# tinyape.net
KiCad netlist of a schematic drawn in EAGLE
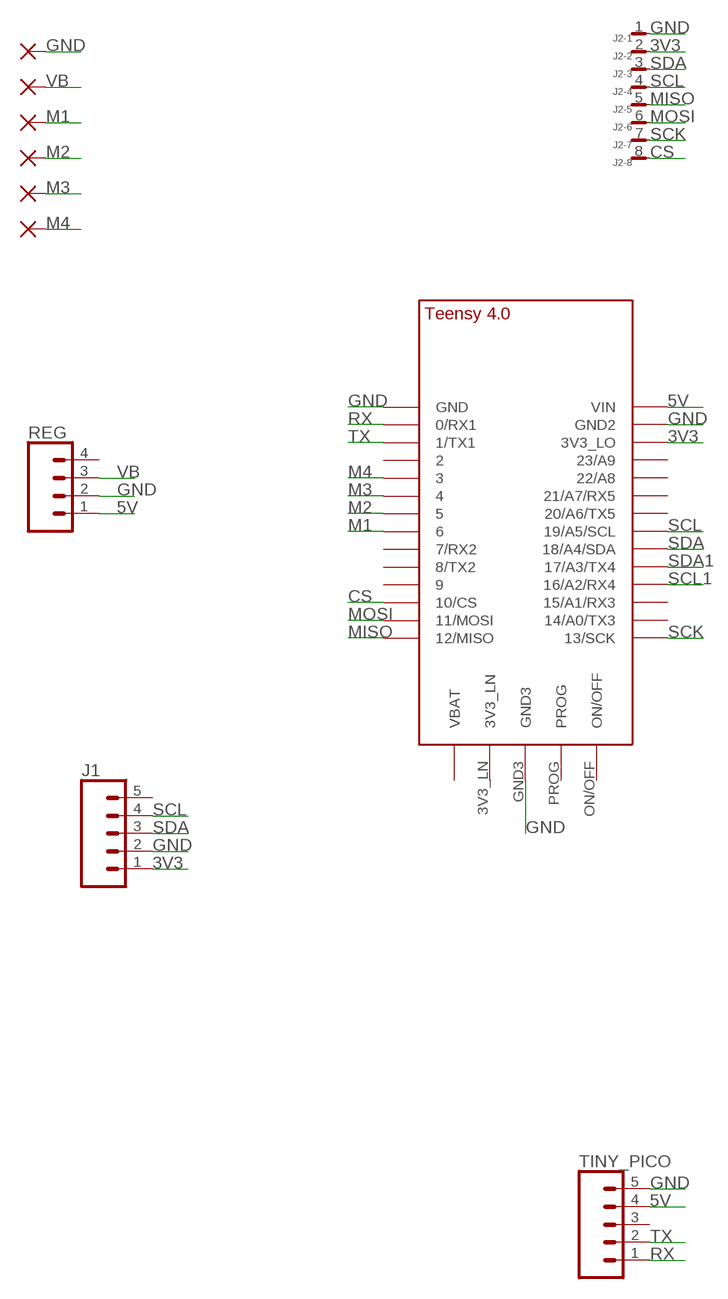
[diagram p0: schematic, sheet 1]

(export (version "E")
  (design (tool "Eeschema 10.0.6"))
  (components
    (comp (ref "GND")
      (value "SMD2")
      (footprint "eagle-import:SMD1,27-2,54")
      (libsource (lib "eagle-import") (part "SMD2"))
    )
    (comp (ref "J1")
      (value "CONN_05NO_SILK")
      (footprint "eagle-import:1X05_NO_SILK")
      (libsource (lib "eagle-import") (part "CONN_05NO_SILK"))
    )
    (comp (ref "J2")
      (value "JST-SH-8_RA")
      (footprint "eagle-import:SM08B-SRSS-TB")
      (fields (field (name "MF") "JST") (field (name "MPN") "SM08B-SRSS-TB"))
      (libsource (lib "eagle-import") (part "JST-SH-8_RA"))
    )
    (comp (ref "M1")
      (value "SMD2")
      (footprint "eagle-import:SMD1,27-2,54")
      (libsource (lib "eagle-import") (part "SMD2"))
    )
    (comp (ref "M2")
      (value "SMD2")
      (footprint "eagle-import:SMD1,27-2,54")
      (libsource (lib "eagle-import") (part "SMD2"))
    )
    (comp (ref "M3")
      (value "SMD2")
      (footprint "eagle-import:SMD1,27-2,54")
      (libsource (lib "eagle-import") (part "SMD2"))
    )
    (comp (ref "M4")
      (value "SMD2")
      (footprint "eagle-import:SMD1,27-2,54")
      (libsource (lib "eagle-import") (part "SMD2"))
    )
    (comp (ref "REG")
      (value "CONN_041X04_NO_SILK")
      (footprint "eagle-import:1X04_NO_SILK")
      (libsource (lib "eagle-import") (part "CONN_041X04_NO_SILK"))
    )
    (comp (ref "TINY_PICO")
      (value "CONN_05NO_SILK")
      (footprint "eagle-import:1X05_NO_SILK")
      (libsource (lib "eagle-import") (part "CONN_05NO_SILK"))
    )
    (comp (ref "U$1")
      (value "TEENSY_4.0")
      (footprint "eagle-import:TEENSY_4.0")
      (libsource (lib "eagle-import") (part "TEENSY_4.0"))
    )
    (comp (ref "VBAT")
      (value "SMD2")
      (footprint "eagle-import:SMD1,27-2,54")
      (libsource (lib "eagle-import") (part "SMD2"))
    )
  )
  (nets
    (net (code "1") (name "/3V3") (class "Default")
      (node (ref "J1") (pin "1") (pinfunction "1_1") (pintype "passive"))
      (node (ref "J2") (pin "2") (pinfunction "P_2") (pintype "bidirectional"))
      (node (ref "U$1") (pin "3V3_LO") (pinfunction "3V3_LO_3V3_LO") (pintype "bidirectional"))
    )
    (net (code "2") (name "/5V") (class "Default")
      (node (ref "REG") (pin "1") (pinfunction "1_1") (pintype "passive"))
      (node (ref "TINY_PICO") (pin "4") (pinfunction "4_4") (pintype "passive"))
      (node (ref "U$1") (pin "VIN") (pinfunction "VIN_VIN") (pintype "bidirectional"))
    )
    (net (code "3") (name "/CS") (class "Default")
      (node (ref "J2") (pin "8") (pinfunction "P_8") (pintype "bidirectional"))
      (node (ref "U$1") (pin "10/CS") (pinfunction "10/CS_10/CS") (pintype "bidirectional"))
    )
    (net (code "4") (name "/GND") (class "Default")
      (node (ref "GND") (pin "1") (pinfunction "P_1") (pintype "passive"))
      (node (ref "J1") (pin "2") (pinfunction "2_2") (pintype "passive"))
      (node (ref "J2") (pin "1") (pinfunction "P_1") (pintype "bidirectional"))
      (node (ref "REG") (pin "2") (pinfunction "2_2") (pintype "passive"))
      (node (ref "TINY_PICO") (pin "5") (pinfunction "5_5") (pintype "passive"))
      (node (ref "U$1") (pin "GND") (pinfunction "GND_GND") (pintype "bidirectional"))
      (node (ref "U$1") (pin "GND2") (pinfunction "GND2_GND2") (pintype "bidirectional"))
      (node (ref "U$1") (pin "GND3") (pinfunction "GND3_GND3") (pintype "bidirectional"))
    )
    (net (code "5") (name "/M1") (class "Default")
      (node (ref "M4") (pin "1") (pinfunction "P_1") (pintype "passive"))
      (node (ref "U$1") (pin "6") (pinfunction "6_6") (pintype "bidirectional"))
    )
    (net (code "6") (name "/M2") (class "Default")
      (node (ref "M3") (pin "1") (pinfunction "P_1") (pintype "passive"))
      (node (ref "U$1") (pin "5") (pinfunction "5_5") (pintype "bidirectional"))
    )
    (net (code "7") (name "/M3") (class "Default")
      (node (ref "M2") (pin "1") (pinfunction "P_1") (pintype "passive"))
      (node (ref "U$1") (pin "4/CANRX") (pinfunction "4_4/CANRX") (pintype "bidirectional"))
    )
    (net (code "8") (name "/M4") (class "Default")
      (node (ref "M1") (pin "1") (pinfunction "P_1") (pintype "passive"))
      (node (ref "U$1") (pin "3/CANTX") (pinfunction "3_3/CANTX") (pintype "bidirectional"))
    )
    (net (code "9") (name "/MISO") (class "Default")
      (node (ref "J2") (pin "5") (pinfunction "P_5") (pintype "bidirectional"))
      (node (ref "U$1") (pin "12/MISO") (pinfunction "12/MISO_12/MISO") (pintype "bidirectional"))
    )
    (net (code "10") (name "/MOSI") (class "Default")
      (node (ref "J2") (pin "6") (pinfunction "P_6") (pintype "bidirectional"))
      (node (ref "U$1") (pin "11/MOSI") (pinfunction "11/MOSI_11/MOSI") (pintype "bidirectional"))
    )
    (net (code "11") (name "/RX") (class "Default")
      (node (ref "TINY_PICO") (pin "1") (pinfunction "1_1") (pintype "passive"))
      (node (ref "U$1") (pin "0/RX") (pinfunction "0/RX1_0/RX") (pintype "bidirectional"))
    )
    (net (code "12") (name "/SCK") (class "Default")
      (node (ref "J2") (pin "7") (pinfunction "P_7") (pintype "bidirectional"))
      (node (ref "U$1") (pin "13/SCK") (pinfunction "13/SCK_13/SCK") (pintype "bidirectional"))
    )
    (net (code "13") (name "/SCL") (class "Default")
      (node (ref "J1") (pin "4") (pinfunction "4_4") (pintype "passive"))
      (node (ref "J2") (pin "4") (pinfunction "P_4") (pintype "bidirectional"))
      (node (ref "U$1") (pin "19/A5/SCL") (pinfunction "19/A5/SCL_19/A5/SCL") (pintype "bidirectional"))
    )
    (net (code "14") (name "/SCL1") (class "Default")
      (node (ref "U$1") (pin "16/A2") (pinfunction "16/A2/RX4_16/A2") (pintype "bidirectional"))
    )
    (net (code "15") (name "/SDA") (class "Default")
      (node (ref "J1") (pin "3") (pinfunction "3_3") (pintype "passive"))
      (node (ref "J2") (pin "3") (pinfunction "P_3") (pintype "bidirectional"))
      (node (ref "U$1") (pin "18/A4/SDA") (pinfunction "18/A4/SDA_18/A4/SDA") (pintype "bidirectional"))
    )
    (net (code "16") (name "/SDA1") (class "Default")
      (node (ref "U$1") (pin "17/A3") (pinfunction "17/A3/TX4_17/A3") (pintype "bidirectional"))
    )
    (net (code "17") (name "/TX") (class "Default")
      (node (ref "TINY_PICO") (pin "2") (pinfunction "2_2") (pintype "passive"))
      (node (ref "U$1") (pin "1/TX") (pinfunction "1/TX1_1/TX") (pintype "bidirectional"))
    )
    (net (code "18") (name "/VB") (class "Default")
      (node (ref "REG") (pin "3") (pinfunction "3_3") (pintype "passive"))
      (node (ref "VBAT") (pin "1") (pinfunction "P_1") (pintype "passive"))
    )
    (net (code "19") (name "unconnected-(J1-Pad5)") (class "Default")
      (node (ref "J1") (pin "5") (pinfunction "5_5") (pintype "passive"))
    )
    (net (code "20") (name "unconnected-(REG-Pad4)") (class "Default")
      (node (ref "REG") (pin "4") (pinfunction "4_4") (pintype "passive"))
    )
    (net (code "21") (name "unconnected-(TINY_PICO-Pad3)") (class "Default")
      (node (ref "TINY_PICO") (pin "3") (pinfunction "3_3") (pintype "passive"))
    )
    (net (code "22") (name "unconnected-(U$1-7{slash}RX2-Pad7)") (class "Default")
      (node (ref "U$1") (pin "7") (pinfunction "7/RX2_7") (pintype "bidirectional"))
    )
    (net (code "23") (name "unconnected-(U$1-8{slash}TX2-Pad8)") (class "Default")
      (node (ref "U$1") (pin "8") (pinfunction "8/TX2_8") (pintype "bidirectional"))
    )
    (net (code "24") (name "unconnected-(U$1-9-Pad9{slash}CS)") (class "Default")
      (node (ref "U$1") (pin "9/CS") (pinfunction "9_9/CS") (pintype "bidirectional"))
    )
    (net (code "25") (name "unconnected-(U$1-14{slash}A0{slash}TX3-Pad14{slash}A0)") (class "Default")
      (node (ref "U$1") (pin "14/A0") (pinfunction "14/A0/TX3_14/A0") (pintype "bidirectional"))
    )
    (net (code "26") (name "unconnected-(U$1-15{slash}A1{slash}RX3-Pad15{slash}A1)") (class "Default")
      (node (ref "U$1") (pin "15/A1") (pinfunction "15/A1/RX3_15/A1") (pintype "bidirectional"))
    )
    (net (code "27") (name "unconnected-(U$1-20{slash}A6{slash}TX5-Pad20{slash}A6)") (class "Default")
      (node (ref "U$1") (pin "20/A6") (pinfunction "20/A6/TX5_20/A6") (pintype "bidirectional"))
    )
    (net (code "28") (name "unconnected-(U$1-21{slash}A7{slash}RX5-Pad21{slash}A7)") (class "Default")
      (node (ref "U$1") (pin "21/A7") (pinfunction "21/A7/RX5_21/A7") (pintype "bidirectional"))
    )
    (net (code "29") (name "unconnected-(U$1-Pad2)") (class "Default")
      (node (ref "U$1") (pin "2") (pinfunction "2_2") (pintype "bidirectional"))
    )
    (net (code "30") (name "unconnected-(U$1-Pad3V3_LN)") (class "Default")
      (node (ref "U$1") (pin "3V3_LN") (pinfunction "3V3_LN_3V3_LN") (pintype "bidirectional"))
    )
    (net (code "31") (name "unconnected-(U$1-Pad22{slash}A8)") (class "Default")
      (node (ref "U$1") (pin "22/A8") (pinfunction "22/A8_22/A8") (pintype "bidirectional"))
    )
    (net (code "32") (name "unconnected-(U$1-Pad23{slash}A9)") (class "Default")
      (node (ref "U$1") (pin "23/A9") (pinfunction "23/A9_23/A9") (pintype "bidirectional"))
    )
    (net (code "33") (name "unconnected-(U$1-PadON{slash}OFF)") (class "Default")
      (node (ref "U$1") (pin "ON/OFF") (pinfunction "ON/OFF_ON/OFF") (pintype "bidirectional"))
    )
    (net (code "34") (name "unconnected-(U$1-PadPROG)") (class "Default")
      (node (ref "U$1") (pin "PROG") (pinfunction "PROG_PROG") (pintype "bidirectional"))
    )
    (net (code "35") (name "unconnected-(U$1-VBAT-PadVBAT\\)") (class "Default")
      (node (ref "U$1") (pin "VBAT\\") (pinfunction "VBAT_VBAT\\") (pintype "bidirectional"))
    )
  )
)
